# V3.net
KiCad netlist of a schematic drawn in Altium Designer
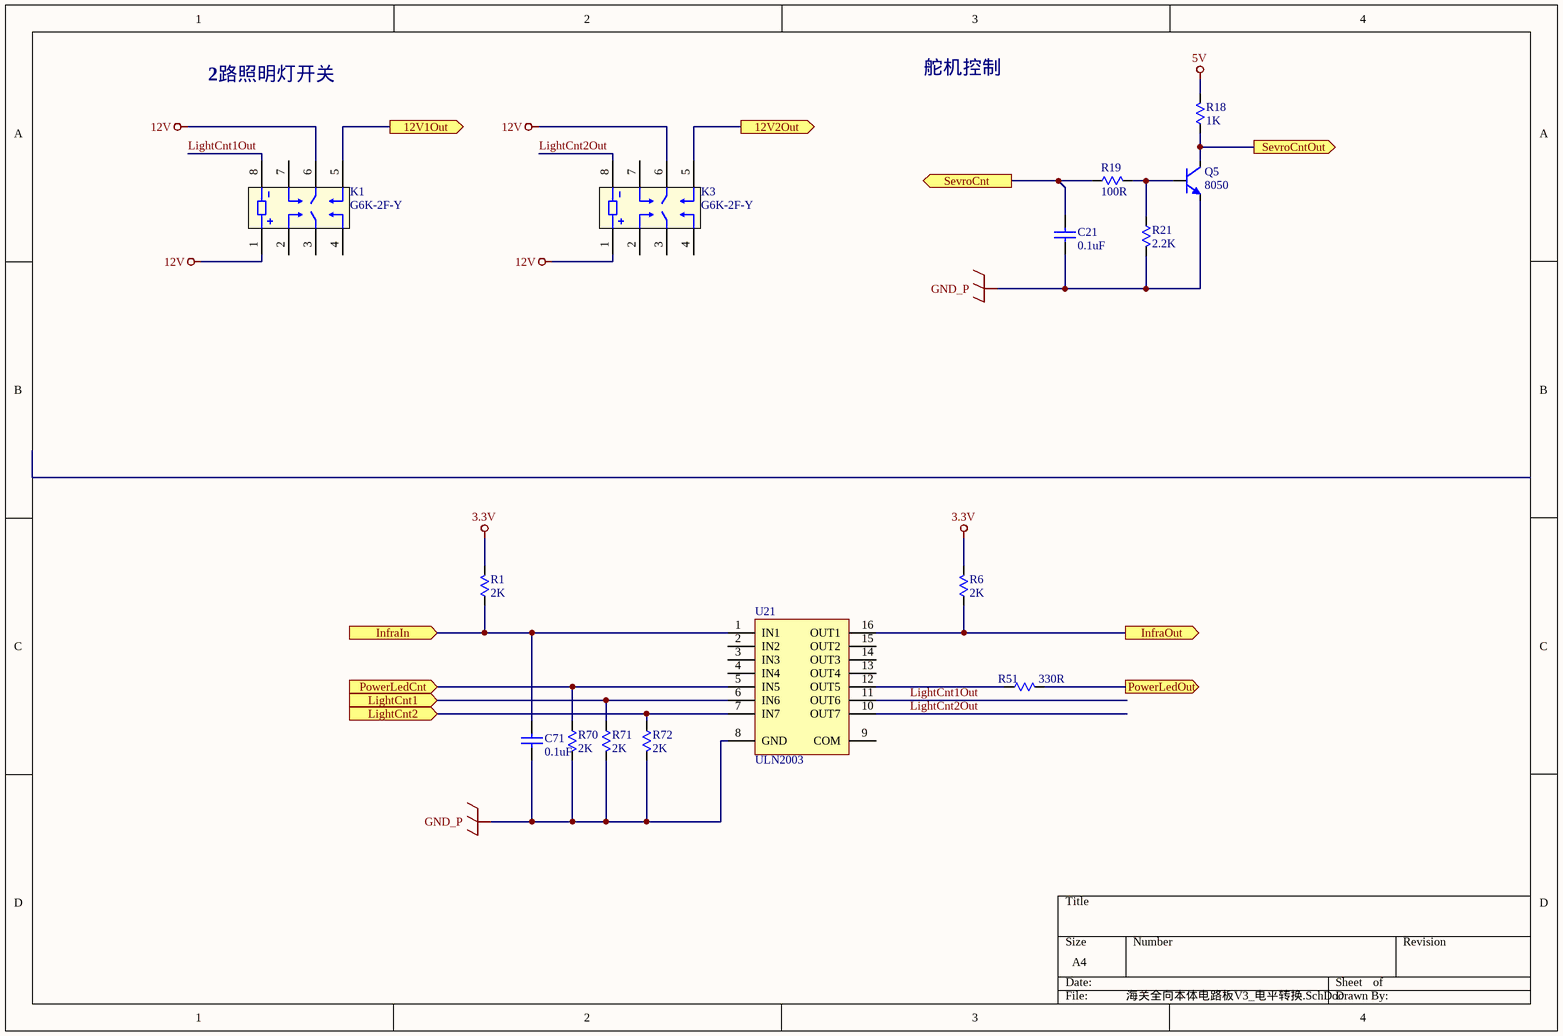
[diagram p0: 海关全向本体电路板V3_电平转换.SchDoc]

(export (version "E")
  (design (tool "Eeschema 10.0.6"))
  (components
    (comp (ref "C21")
      (value "0.1uF")
      (footprint "C0603-S")
      (description "Capacitor")
      (fields (field (name "PUBLISHER") "Altium Limited"))
      (libsource (lib "Miscellaneous Devices") (part "Cap"))
    )
    (comp (ref "C71")
      (value "0.1uF")
      (footprint "C0603-S")
      (description "Capacitor")
      (fields (field (name "PUBLISHER") "Altium Limited"))
      (libsource (lib "Miscellaneous Devices") (part "Cap"))
    )
    (comp (ref "K1")
      (value "G6K-2F-Y")
      (footprint "G6K-2F-Y")
      (libsource (lib "Productor Class") (part "G6K-2F-Y"))
    )
    (comp (ref "K3")
      (value "G6K-2F-Y")
      (footprint "G6K-2F-Y")
      (libsource (lib "Productor Class") (part "G6K-2F-Y"))
    )
    (comp (ref "Q5")
      (value "8050")
      (footprint "SOT-23")
      (description "NPN General Purpose Amplifier")
      (fields (field (name "PUBLISHER") "Altium Limited"))
      (libsource (lib "Bdmc4810") (part "NPN"))
    )
    (comp (ref "R1")
      (value "2K")
      (footprint "R0603-S")
      (description "Resistor")
      (fields (field (name "PUBLISHER") "Altium Limited"))
      (libsource (lib "Temp") (part "Res"))
    )
    (comp (ref "R6")
      (value "2K")
      (footprint "R0603-S")
      (description "Resistor")
      (fields (field (name "PUBLISHER") "Altium Limited"))
      (libsource (lib "Temp") (part "Res"))
    )
    (comp (ref "R18")
      (value "1K")
      (footprint "R0603-S")
      (description "Resistor")
      (fields (field (name "PUBLISHER") "Altium Limited"))
      (libsource (lib "Passive Components Class") (part "RES"))
    )
    (comp (ref "R19")
      (value "100R")
      (footprint "R0603-S")
      (description "Resistor")
      (fields (field (name "PUBLISHER") "Altium Limited"))
      (libsource (lib "Passive Components Class") (part "RES"))
    )
    (comp (ref "R21")
      (value "2.2K")
      (footprint "R0603-S")
      (description "Resistor")
      (fields (field (name "PUBLISHER") "Altium Limited"))
      (libsource (lib "Temp") (part "Res"))
    )
    (comp (ref "R51")
      (value "330R")
      (footprint "R0603-S")
      (description "Resistor")
      (fields (field (name "PUBLISHER") "Altium Limited"))
      (libsource (lib "Temp") (part "Res"))
    )
    (comp (ref "R70")
      (value "2K")
      (footprint "R0603-S")
      (description "Resistor")
      (fields (field (name "PUBLISHER") "Altium Limited"))
      (libsource (lib "Temp") (part "Res"))
    )
    (comp (ref "R71")
      (value "2K")
      (footprint "R0603-S")
      (description "Resistor")
      (fields (field (name "PUBLISHER") "Altium Limited"))
      (libsource (lib "Temp") (part "Res"))
    )
    (comp (ref "R72")
      (value "2K")
      (footprint "R0603-S")
      (description "Resistor")
      (fields (field (name "PUBLISHER") "Altium Limited"))
      (libsource (lib "Temp") (part "Res"))
    )
    (comp (ref "U21")
      (value "ULN2003")
      (footprint "SO16-150")
      (libsource (lib "Logic Class") (part "ULN2003"))
    )
  )
  (nets
    (net (code "1") (name "/12V1Out") (class "Default")
      (node (ref "K1") (pin "5") (pinfunction "5_5") (pintype "passive"))
    )
    (net (code "2") (name "/12V2Out") (class "Default")
      (node (ref "K3") (pin "5") (pinfunction "5_5") (pintype "passive"))
    )
    (net (code "3") (name "/InfraIn") (class "Default")
      (node (ref "C71") (pin "2") (pinfunction "2_2") (pintype "passive"))
      (node (ref "R1") (pin "2") (pinfunction "2_2") (pintype "passive"))
      (node (ref "U21") (pin "1") (pinfunction "IN1_1") (pintype "passive"))
    )
    (net (code "4") (name "/InfraOut") (class "Default")
      (node (ref "R6") (pin "2") (pinfunction "2_2") (pintype "passive"))
      (node (ref "U21") (pin "16") (pinfunction "OUT1_16") (pintype "open_collector"))
    )
    (net (code "5") (name "/LightCnt1") (class "Default")
      (node (ref "R71") (pin "2") (pinfunction "2_2") (pintype "passive"))
      (node (ref "U21") (pin "6") (pinfunction "IN6_6") (pintype "passive"))
    )
    (net (code "6") (name "/LightCnt1Out") (class "Default")
      (node (ref "K1") (pin "8") (pinfunction "8_8") (pintype "passive"))
      (node (ref "U21") (pin "11") (pinfunction "OUT6_11") (pintype "open_collector"))
    )
    (net (code "7") (name "/LightCnt2") (class "Default")
      (node (ref "R72") (pin "2") (pinfunction "2_2") (pintype "passive"))
      (node (ref "U21") (pin "7") (pinfunction "IN7_7") (pintype "passive"))
    )
    (net (code "8") (name "/LightCnt2Out") (class "Default")
      (node (ref "K3") (pin "8") (pinfunction "8_8") (pintype "passive"))
      (node (ref "U21") (pin "10") (pinfunction "OUT7_10") (pintype "open_collector"))
    )
    (net (code "9") (name "/PowerLedCnt") (class "Default")
      (node (ref "R70") (pin "2") (pinfunction "2_2") (pintype "passive"))
      (node (ref "U21") (pin "5") (pinfunction "IN5_5") (pintype "passive"))
    )
    (net (code "10") (name "/PowerLedOut") (class "Default")
      (node (ref "R51") (pin "1") (pinfunction "1_1") (pintype "passive"))
    )
    (net (code "11") (name "/SevroCnt") (class "Default")
      (node (ref "C21") (pin "2") (pinfunction "2_2") (pintype "passive"))
      (node (ref "R19") (pin "2") (pinfunction "2_2") (pintype "passive"))
    )
    (net (code "12") (name "/SevroCntOut") (class "Default")
      (node (ref "Q5") (pin "3") (pinfunction "C_3") (pintype "passive"))
      (node (ref "R18") (pin "2") (pinfunction "2_2") (pintype "passive"))
    )
    (net (code "13") (name "3.3V") (class "Default")
      (node (ref "R1") (pin "1") (pinfunction "1_1") (pintype "passive"))
      (node (ref "R6") (pin "1") (pinfunction "1_1") (pintype "passive"))
    )
    (net (code "14") (name "5V") (class "Default")
      (node (ref "R18") (pin "1") (pinfunction "1_1") (pintype "passive"))
    )
    (net (code "15") (name "12V") (class "Default")
      (node (ref "K1") (pin "1") (pinfunction "1_1") (pintype "passive"))
      (node (ref "K1") (pin "6") (pinfunction "6_6") (pintype "passive"))
      (node (ref "K3") (pin "1") (pinfunction "1_1") (pintype "passive"))
      (node (ref "K3") (pin "6") (pinfunction "6_6") (pintype "passive"))
    )
    (net (code "16") (name "GND_P") (class "Default")
      (node (ref "C21") (pin "1") (pinfunction "1_1") (pintype "passive"))
      (node (ref "C71") (pin "1") (pinfunction "1_1") (pintype "passive"))
      (node (ref "Q5") (pin "2") (pinfunction "E_2") (pintype "passive"))
      (node (ref "R21") (pin "1") (pinfunction "1_1") (pintype "passive"))
      (node (ref "R70") (pin "1") (pinfunction "1_1") (pintype "passive"))
      (node (ref "R71") (pin "1") (pinfunction "1_1") (pintype "passive"))
      (node (ref "R72") (pin "1") (pinfunction "1_1") (pintype "passive"))
      (node (ref "U21") (pin "8") (pinfunction "GND_8") (pintype "power_in"))
    )
    (net (code "17") (name "Net-(Q5-B)") (class "Default")
      (node (ref "Q5") (pin "1") (pinfunction "B_1") (pintype "passive"))
      (node (ref "R19") (pin "1") (pinfunction "1_1") (pintype "passive"))
      (node (ref "R21") (pin "2") (pinfunction "2_2") (pintype "passive"))
    )
    (net (code "18") (name "Net-(U21-OUT5)") (class "Default")
      (node (ref "R51") (pin "2") (pinfunction "2_2") (pintype "passive"))
      (node (ref "U21") (pin "12") (pinfunction "OUT5_12") (pintype "open_collector"))
    )
    (net (code "19") (name "unconnected-(K1-Pad2)") (class "Default")
      (node (ref "K1") (pin "2") (pinfunction "2_2") (pintype "passive"))
    )
    (net (code "20") (name "unconnected-(K1-Pad3)") (class "Default")
      (node (ref "K1") (pin "3") (pinfunction "3_3") (pintype "passive"))
    )
    (net (code "21") (name "unconnected-(K1-Pad4)") (class "Default")
      (node (ref "K1") (pin "4") (pinfunction "4_4") (pintype "passive"))
    )
    (net (code "22") (name "unconnected-(K1-Pad7)") (class "Default")
      (node (ref "K1") (pin "7") (pinfunction "7_7") (pintype "passive"))
    )
    (net (code "23") (name "unconnected-(K3-Pad2)") (class "Default")
      (node (ref "K3") (pin "2") (pinfunction "2_2") (pintype "passive"))
    )
    (net (code "24") (name "unconnected-(K3-Pad3)") (class "Default")
      (node (ref "K3") (pin "3") (pinfunction "3_3") (pintype "passive"))
    )
    (net (code "25") (name "unconnected-(K3-Pad4)") (class "Default")
      (node (ref "K3") (pin "4") (pinfunction "4_4") (pintype "passive"))
    )
    (net (code "26") (name "unconnected-(K3-Pad7)") (class "Default")
      (node (ref "K3") (pin "7") (pinfunction "7_7") (pintype "passive"))
    )
    (net (code "27") (name "unconnected-(U21-COM-Pad9)") (class "Default")
      (node (ref "U21") (pin "9") (pinfunction "COM_9") (pintype "passive"))
    )
    (net (code "28") (name "unconnected-(U21-IN2-Pad2)") (class "Default")
      (node (ref "U21") (pin "2") (pinfunction "IN2_2") (pintype "passive"))
    )
    (net (code "29") (name "unconnected-(U21-IN3-Pad3)") (class "Default")
      (node (ref "U21") (pin "3") (pinfunction "IN3_3") (pintype "passive"))
    )
    (net (code "30") (name "unconnected-(U21-IN4-Pad4)") (class "Default")
      (node (ref "U21") (pin "4") (pinfunction "IN4_4") (pintype "passive"))
    )
    (net (code "31") (name "unconnected-(U21-OUT2-Pad15)") (class "Default")
      (node (ref "U21") (pin "15") (pinfunction "OUT2_15") (pintype "open_collector"))
    )
    (net (code "32") (name "unconnected-(U21-OUT3-Pad14)") (class "Default")
      (node (ref "U21") (pin "14") (pinfunction "OUT3_14") (pintype "open_collector"))
    )
    (net (code "33") (name "unconnected-(U21-OUT4-Pad13)") (class "Default")
      (node (ref "U21") (pin "13") (pinfunction "OUT4_13") (pintype "open_collector"))
    )
  )
)
